# timer_v2.net
KiCad netlist of a schematic drawn in EAGLE
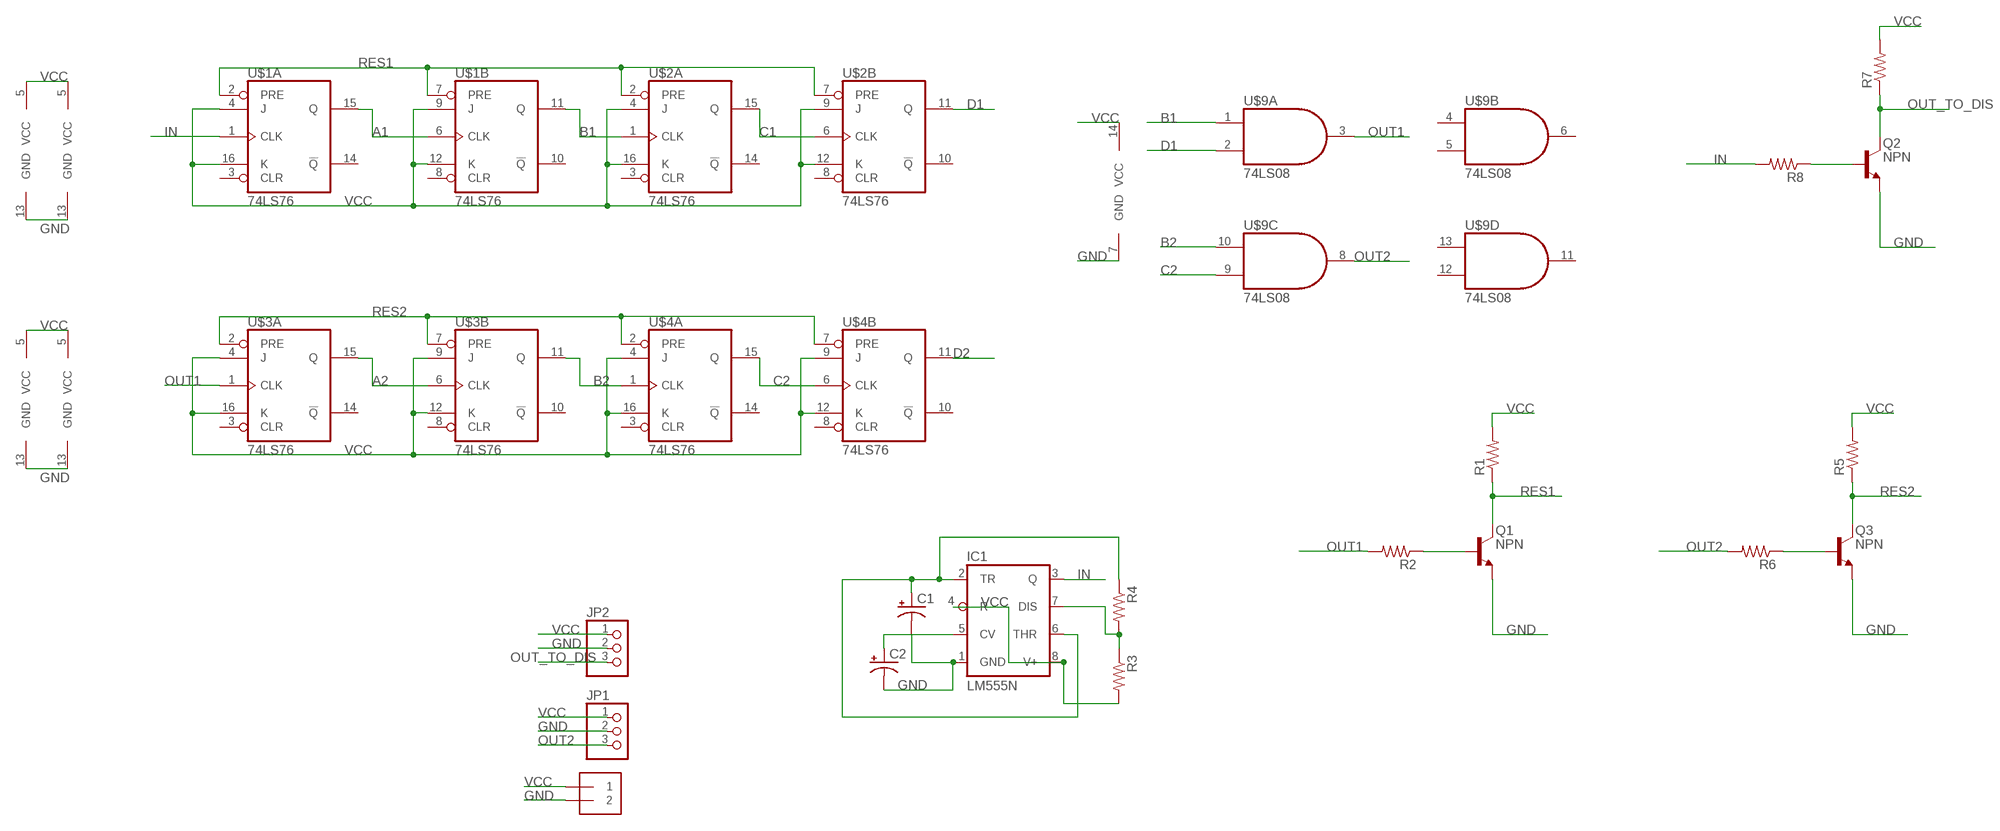
[diagram p0: schematic, sheet 1]

(export (version "E")
  (design (tool "Eeschema 10.0.6"))
  (components
    (comp (ref "C1")
      (value "C-POL-US_RADIAL-20MM-DIA")
      (footprint "eagle-import:CAPPRD550W60D1200H2000B")
      (libsource (lib "eagle-import") (part "C-POL-USRADIAL-20MM-DIA_"))
    )
    (comp (ref "C2")
      (value "C-POL-US_RADIAL-20MM-DIA")
      (footprint "eagle-import:CAPPRD550W60D1200H2000B")
      (libsource (lib "eagle-import") (part "C-POL-USRADIAL-20MM-DIA_"))
    )
    (comp (ref "IC1")
      (value "LM555N")
      (footprint "eagle-import:DIL08-ROUND")
      (libsource (lib "eagle-import") (part "555NLM"))
    )
    (comp (ref "J1")
      (value "1X2-3.5MM")
      (footprint "eagle-import:1X2-3.5MM")
      (libsource (lib "eagle-import") (part "1X2-3.5MM"))
    )
    (comp (ref "JP1")
      (value "PINHD-1X3CB")
      (footprint "eagle-import:1X03-CLEANBIG")
      (libsource (lib "eagle-import") (part "PINHD-1X3CB"))
    )
    (comp (ref "JP2")
      (value "PINHD-1X3CB")
      (footprint "eagle-import:1X03-CLEANBIG")
      (libsource (lib "eagle-import") (part "PINHD-1X3CB"))
    )
    (comp (ref "Q1")
      (value "NPN")
      (footprint "eagle-import:TO92")
      (libsource (lib "eagle-import") (part "NPNTO92-EBC_"))
    )
    (comp (ref "Q2")
      (value "NPN")
      (footprint "eagle-import:TO92")
      (libsource (lib "eagle-import") (part "NPNTO92-EBC_"))
    )
    (comp (ref "Q3")
      (value "NPN")
      (footprint "eagle-import:TO92")
      (libsource (lib "eagle-import") (part "NPNTO92-EBC_"))
    )
    (comp (ref "R1")
      (value "R-US_AXIAL-7.2MM-PITCH")
      (footprint "eagle-import:RESAD724W46L381D178B")
      (libsource (lib "eagle-import") (part "R-USAXIAL-7.2MM-PITCH_"))
    )
    (comp (ref "R2")
      (value "R-US_AXIAL-7.2MM-PITCH")
      (footprint "eagle-import:RESAD724W46L381D178B")
      (libsource (lib "eagle-import") (part "R-USAXIAL-7.2MM-PITCH_"))
    )
    (comp (ref "R3")
      (value "R-US_AXIAL-7.2MM-PITCH")
      (footprint "eagle-import:RESAD724W46L381D178B")
      (libsource (lib "eagle-import") (part "R-USAXIAL-7.2MM-PITCH_"))
    )
    (comp (ref "R4")
      (value "R-US_AXIAL-7.2MM-PITCH")
      (footprint "eagle-import:RESAD724W46L381D178B")
      (libsource (lib "eagle-import") (part "R-USAXIAL-7.2MM-PITCH_"))
    )
    (comp (ref "R5")
      (value "R-US_AXIAL-7.2MM-PITCH")
      (footprint "eagle-import:RESAD724W46L381D178B")
      (libsource (lib "eagle-import") (part "R-USAXIAL-7.2MM-PITCH_"))
    )
    (comp (ref "R6")
      (value "R-US_AXIAL-7.2MM-PITCH")
      (footprint "eagle-import:RESAD724W46L381D178B")
      (libsource (lib "eagle-import") (part "R-USAXIAL-7.2MM-PITCH_"))
    )
    (comp (ref "R7")
      (value "R-US_AXIAL-7.2MM-PITCH")
      (footprint "eagle-import:RESAD724W46L381D178B")
      (libsource (lib "eagle-import") (part "R-USAXIAL-7.2MM-PITCH_"))
    )
    (comp (ref "R8")
      (value "R-US_AXIAL-7.2MM-PITCH")
      (footprint "eagle-import:RESAD724W46L381D178B")
      (libsource (lib "eagle-import") (part "R-USAXIAL-7.2MM-PITCH_"))
    )
    (comp (ref "U$1")
      (value "74LS76")
      (footprint "eagle-import:DIO16")
      (libsource (lib "eagle-import") (part "74LS76"))
    )
    (comp (ref "U$2")
      (value "74LS76")
      (footprint "eagle-import:DIO16")
      (libsource (lib "eagle-import") (part "74LS76"))
    )
    (comp (ref "U$3")
      (value "74LS76")
      (footprint "eagle-import:DIO16")
      (libsource (lib "eagle-import") (part "74LS76"))
    )
    (comp (ref "U$4")
      (value "74LS76")
      (footprint "eagle-import:DIO16")
      (libsource (lib "eagle-import") (part "74LS76"))
    )
    (comp (ref "U$9")
      (value "74LS08")
      (footprint "eagle-import:DIO14")
      (libsource (lib "eagle-import") (part "74LS08"))
    )
  )
  (nets
    (net (code "1") (name "/A1") (class "Default")
      (node (ref "U$1") (pin "15") (pinfunction "Q_15") (pintype "output"))
      (node (ref "U$1") (pin "6") (pinfunction "CLK_6") (pintype "input"))
    )
    (net (code "2") (name "/A2") (class "Default")
      (node (ref "U$3") (pin "15") (pinfunction "Q_15") (pintype "output"))
      (node (ref "U$3") (pin "6") (pinfunction "CLK_6") (pintype "input"))
    )
    (net (code "3") (name "/B1") (class "Default")
      (node (ref "U$1") (pin "11") (pinfunction "Q_11") (pintype "output"))
      (node (ref "U$2") (pin "1") (pinfunction "CLK_1") (pintype "input"))
      (node (ref "U$9") (pin "1") (pinfunction "I0_1") (pintype "input"))
    )
    (net (code "4") (name "/B2") (class "Default")
      (node (ref "U$3") (pin "11") (pinfunction "Q_11") (pintype "output"))
      (node (ref "U$4") (pin "1") (pinfunction "CLK_1") (pintype "input"))
      (node (ref "U$9") (pin "10") (pinfunction "I0_10") (pintype "input"))
    )
    (net (code "5") (name "/C1") (class "Default")
      (node (ref "U$2") (pin "15") (pinfunction "Q_15") (pintype "output"))
      (node (ref "U$2") (pin "6") (pinfunction "CLK_6") (pintype "input"))
    )
    (net (code "6") (name "/C2") (class "Default")
      (node (ref "U$4") (pin "15") (pinfunction "Q_15") (pintype "output"))
      (node (ref "U$4") (pin "6") (pinfunction "CLK_6") (pintype "input"))
      (node (ref "U$9") (pin "9") (pinfunction "I1_9") (pintype "input"))
    )
    (net (code "7") (name "/D1") (class "Default")
      (node (ref "U$2") (pin "11") (pinfunction "Q_11") (pintype "output"))
      (node (ref "U$9") (pin "2") (pinfunction "I1_2") (pintype "input"))
    )
    (net (code "8") (name "/D2") (class "Default")
      (node (ref "U$4") (pin "11") (pinfunction "Q_11") (pintype "output"))
    )
    (net (code "9") (name "/GND") (class "Default")
      (node (ref "C1") (pin "2") (pinfunction "-_2") (pintype "passive"))
      (node (ref "C2") (pin "2") (pinfunction "-_2") (pintype "passive"))
      (node (ref "IC1") (pin "1") (pinfunction "GND_1") (pintype "power_in"))
      (node (ref "J1") (pin "2") (pinfunction "2_2") (pintype "passive"))
      (node (ref "JP1") (pin "2") (pinfunction "2_2") (pintype "passive"))
      (node (ref "JP2") (pin "2") (pinfunction "2_2") (pintype "passive"))
      (node (ref "Q1") (pin "1") (pinfunction "E_1") (pintype "passive"))
      (node (ref "Q2") (pin "1") (pinfunction "E_1") (pintype "passive"))
      (node (ref "Q3") (pin "1") (pinfunction "E_1") (pintype "passive"))
      (node (ref "U$1") (pin "13") (pinfunction "GND_13") (pintype "bidirectional"))
      (node (ref "U$2") (pin "13") (pinfunction "GND_13") (pintype "bidirectional"))
      (node (ref "U$3") (pin "13") (pinfunction "GND_13") (pintype "bidirectional"))
      (node (ref "U$4") (pin "13") (pinfunction "GND_13") (pintype "bidirectional"))
      (node (ref "U$9") (pin "7") (pinfunction "GND_7") (pintype "bidirectional"))
    )
    (net (code "10") (name "/IN") (class "Default")
      (node (ref "IC1") (pin "3") (pinfunction "Q_3") (pintype "output"))
      (node (ref "R8") (pin "2") (pinfunction "2_2") (pintype "passive"))
      (node (ref "U$1") (pin "1") (pinfunction "CLK_1") (pintype "input"))
    )
    (net (code "11") (name "/OUT1") (class "Default")
      (node (ref "R2") (pin "2") (pinfunction "2_2") (pintype "passive"))
      (node (ref "U$3") (pin "1") (pinfunction "CLK_1") (pintype "input"))
      (node (ref "U$9") (pin "3") (pinfunction "O_3") (pintype "output"))
    )
    (net (code "12") (name "/OUT2") (class "Default")
      (node (ref "JP1") (pin "3") (pinfunction "3_3") (pintype "passive"))
      (node (ref "R6") (pin "2") (pinfunction "2_2") (pintype "passive"))
      (node (ref "U$9") (pin "8") (pinfunction "O_8") (pintype "output"))
    )
    (net (code "13") (name "/OUT_TO_DIS") (class "Default")
      (node (ref "JP2") (pin "3") (pinfunction "3_3") (pintype "passive"))
      (node (ref "Q2") (pin "3") (pinfunction "C_3") (pintype "passive"))
      (node (ref "R7") (pin "1") (pinfunction "1_1") (pintype "passive"))
    )
    (net (code "14") (name "/RES1") (class "Default")
      (node (ref "Q1") (pin "3") (pinfunction "C_3") (pintype "passive"))
      (node (ref "R1") (pin "1") (pinfunction "1_1") (pintype "passive"))
      (node (ref "U$1") (pin "2") (pinfunction "PRE_2") (pintype "input"))
      (node (ref "U$1") (pin "7") (pinfunction "PRE_7") (pintype "input"))
      (node (ref "U$2") (pin "2") (pinfunction "PRE_2") (pintype "input"))
      (node (ref "U$2") (pin "7") (pinfunction "PRE_7") (pintype "input"))
    )
    (net (code "15") (name "/RES2") (class "Default")
      (node (ref "Q3") (pin "3") (pinfunction "C_3") (pintype "passive"))
      (node (ref "R5") (pin "1") (pinfunction "1_1") (pintype "passive"))
      (node (ref "U$3") (pin "2") (pinfunction "PRE_2") (pintype "input"))
      (node (ref "U$3") (pin "7") (pinfunction "PRE_7") (pintype "input"))
      (node (ref "U$4") (pin "2") (pinfunction "PRE_2") (pintype "input"))
      (node (ref "U$4") (pin "7") (pinfunction "PRE_7") (pintype "input"))
    )
    (net (code "16") (name "/VCC") (class "Default")
      (node (ref "IC1") (pin "4") (pinfunction "R_4") (pintype "input"))
      (node (ref "IC1") (pin "8") (pinfunction "V+_8") (pintype "power_in"))
      (node (ref "J1") (pin "1") (pinfunction "1_1") (pintype "passive"))
      (node (ref "JP1") (pin "1") (pinfunction "1_1") (pintype "passive"))
      (node (ref "JP2") (pin "1") (pinfunction "1_1") (pintype "passive"))
      (node (ref "R1") (pin "2") (pinfunction "2_2") (pintype "passive"))
      (node (ref "R3") (pin "2") (pinfunction "2_2") (pintype "passive"))
      (node (ref "R5") (pin "2") (pinfunction "2_2") (pintype "passive"))
      (node (ref "R7") (pin "2") (pinfunction "2_2") (pintype "passive"))
      (node (ref "U$1") (pin "12") (pinfunction "K_12") (pintype "input"))
      (node (ref "U$1") (pin "16") (pinfunction "K_16") (pintype "input"))
      (node (ref "U$1") (pin "4") (pinfunction "J_4") (pintype "input"))
      (node (ref "U$1") (pin "5") (pinfunction "VCC_5") (pintype "bidirectional"))
      (node (ref "U$1") (pin "9") (pinfunction "J_9") (pintype "input"))
      (node (ref "U$2") (pin "12") (pinfunction "K_12") (pintype "input"))
      (node (ref "U$2") (pin "16") (pinfunction "K_16") (pintype "input"))
      (node (ref "U$2") (pin "4") (pinfunction "J_4") (pintype "input"))
      (node (ref "U$2") (pin "5") (pinfunction "VCC_5") (pintype "bidirectional"))
      (node (ref "U$2") (pin "9") (pinfunction "J_9") (pintype "input"))
      (node (ref "U$3") (pin "12") (pinfunction "K_12") (pintype "input"))
      (node (ref "U$3") (pin "16") (pinfunction "K_16") (pintype "input"))
      (node (ref "U$3") (pin "4") (pinfunction "J_4") (pintype "input"))
      (node (ref "U$3") (pin "5") (pinfunction "VCC_5") (pintype "bidirectional"))
      (node (ref "U$3") (pin "9") (pinfunction "J_9") (pintype "input"))
      (node (ref "U$4") (pin "12") (pinfunction "K_12") (pintype "input"))
      (node (ref "U$4") (pin "16") (pinfunction "K_16") (pintype "input"))
      (node (ref "U$4") (pin "4") (pinfunction "J_4") (pintype "input"))
      (node (ref "U$4") (pin "5") (pinfunction "VCC_5") (pintype "bidirectional"))
      (node (ref "U$4") (pin "9") (pinfunction "J_9") (pintype "input"))
      (node (ref "U$9") (pin "14") (pinfunction "VCC_14") (pintype "bidirectional"))
    )
    (net (code "17") (name "Net-(C1-+)") (class "Default")
      (node (ref "C1") (pin "1") (pinfunction "+_1") (pintype "passive"))
      (node (ref "IC1") (pin "2") (pinfunction "TR_2") (pintype "input"))
      (node (ref "IC1") (pin "6") (pinfunction "THR_6") (pintype "input"))
      (node (ref "R4") (pin "1") (pinfunction "1_1") (pintype "passive"))
    )
    (net (code "18") (name "Net-(C2-+)") (class "Default")
      (node (ref "C2") (pin "1") (pinfunction "+_1") (pintype "passive"))
      (node (ref "IC1") (pin "5") (pinfunction "CV_5") (pintype "input"))
    )
    (net (code "19") (name "Net-(IC1-DIS)") (class "Default")
      (node (ref "IC1") (pin "7") (pinfunction "DIS_7") (pintype "input"))
      (node (ref "R3") (pin "1") (pinfunction "1_1") (pintype "passive"))
      (node (ref "R4") (pin "2") (pinfunction "2_2") (pintype "passive"))
    )
    (net (code "20") (name "Net-(Q1-B)") (class "Default")
      (node (ref "Q1") (pin "2") (pinfunction "B_2") (pintype "passive"))
      (node (ref "R2") (pin "1") (pinfunction "1_1") (pintype "passive"))
    )
    (net (code "21") (name "Net-(Q2-B)") (class "Default")
      (node (ref "Q2") (pin "2") (pinfunction "B_2") (pintype "passive"))
      (node (ref "R8") (pin "1") (pinfunction "1_1") (pintype "passive"))
    )
    (net (code "22") (name "Net-(Q3-B)") (class "Default")
      (node (ref "Q3") (pin "2") (pinfunction "B_2") (pintype "passive"))
      (node (ref "R6") (pin "1") (pinfunction "1_1") (pintype "passive"))
    )
    (net (code "23") (name "unconnected-(U$1A-CLR-Pad3)") (class "Default")
      (node (ref "U$1") (pin "3") (pinfunction "CLR_3") (pintype "input"))
    )
    (net (code "24") (name "unconnected-(U$1A-~{Q}-Pad14)") (class "Default")
      (node (ref "U$1") (pin "14") (pinfunction "~{Q}_14") (pintype "output"))
    )
    (net (code "25") (name "unconnected-(U$1B-CLR-Pad8)") (class "Default")
      (node (ref "U$1") (pin "8") (pinfunction "CLR_8") (pintype "input"))
    )
    (net (code "26") (name "unconnected-(U$1B-~{Q}-Pad10)") (class "Default")
      (node (ref "U$1") (pin "10") (pinfunction "~{Q}_10") (pintype "output"))
    )
    (net (code "27") (name "unconnected-(U$2A-CLR-Pad3)") (class "Default")
      (node (ref "U$2") (pin "3") (pinfunction "CLR_3") (pintype "input"))
    )
    (net (code "28") (name "unconnected-(U$2A-~{Q}-Pad14)") (class "Default")
      (node (ref "U$2") (pin "14") (pinfunction "~{Q}_14") (pintype "output"))
    )
    (net (code "29") (name "unconnected-(U$2B-CLR-Pad8)") (class "Default")
      (node (ref "U$2") (pin "8") (pinfunction "CLR_8") (pintype "input"))
    )
    (net (code "30") (name "unconnected-(U$2B-~{Q}-Pad10)") (class "Default")
      (node (ref "U$2") (pin "10") (pinfunction "~{Q}_10") (pintype "output"))
    )
    (net (code "31") (name "unconnected-(U$3A-CLR-Pad3)") (class "Default")
      (node (ref "U$3") (pin "3") (pinfunction "CLR_3") (pintype "input"))
    )
    (net (code "32") (name "unconnected-(U$3A-~{Q}-Pad14)") (class "Default")
      (node (ref "U$3") (pin "14") (pinfunction "~{Q}_14") (pintype "output"))
    )
    (net (code "33") (name "unconnected-(U$3B-CLR-Pad8)") (class "Default")
      (node (ref "U$3") (pin "8") (pinfunction "CLR_8") (pintype "input"))
    )
    (net (code "34") (name "unconnected-(U$3B-~{Q}-Pad10)") (class "Default")
      (node (ref "U$3") (pin "10") (pinfunction "~{Q}_10") (pintype "output"))
    )
    (net (code "35") (name "unconnected-(U$4A-CLR-Pad3)") (class "Default")
      (node (ref "U$4") (pin "3") (pinfunction "CLR_3") (pintype "input"))
    )
    (net (code "36") (name "unconnected-(U$4A-~{Q}-Pad14)") (class "Default")
      (node (ref "U$4") (pin "14") (pinfunction "~{Q}_14") (pintype "output"))
    )
    (net (code "37") (name "unconnected-(U$4B-CLR-Pad8)") (class "Default")
      (node (ref "U$4") (pin "8") (pinfunction "CLR_8") (pintype "input"))
    )
    (net (code "38") (name "unconnected-(U$4B-~{Q}-Pad10)") (class "Default")
      (node (ref "U$4") (pin "10") (pinfunction "~{Q}_10") (pintype "output"))
    )
    (net (code "39") (name "unconnected-(U$9B-I0-Pad4)") (class "Default")
      (node (ref "U$9") (pin "4") (pinfunction "I0_4") (pintype "input"))
    )
    (net (code "40") (name "unconnected-(U$9B-I1-Pad5)") (class "Default")
      (node (ref "U$9") (pin "5") (pinfunction "I1_5") (pintype "input"))
    )
    (net (code "41") (name "unconnected-(U$9B-O-Pad6)") (class "Default")
      (node (ref "U$9") (pin "6") (pinfunction "O_6") (pintype "output"))
    )
    (net (code "42") (name "unconnected-(U$9D-I0-Pad13)") (class "Default")
      (node (ref "U$9") (pin "13") (pinfunction "I0_13") (pintype "input"))
    )
    (net (code "43") (name "unconnected-(U$9D-I1-Pad12)") (class "Default")
      (node (ref "U$9") (pin "12") (pinfunction "I1_12") (pintype "input"))
    )
    (net (code "44") (name "unconnected-(U$9D-O-Pad11)") (class "Default")
      (node (ref "U$9") (pin "11") (pinfunction "O_11") (pintype "output"))
    )
  )
)
